# HEBoard_schematic_Ver3.net
KiCad netlist of a schematic drawn in Altium Designer
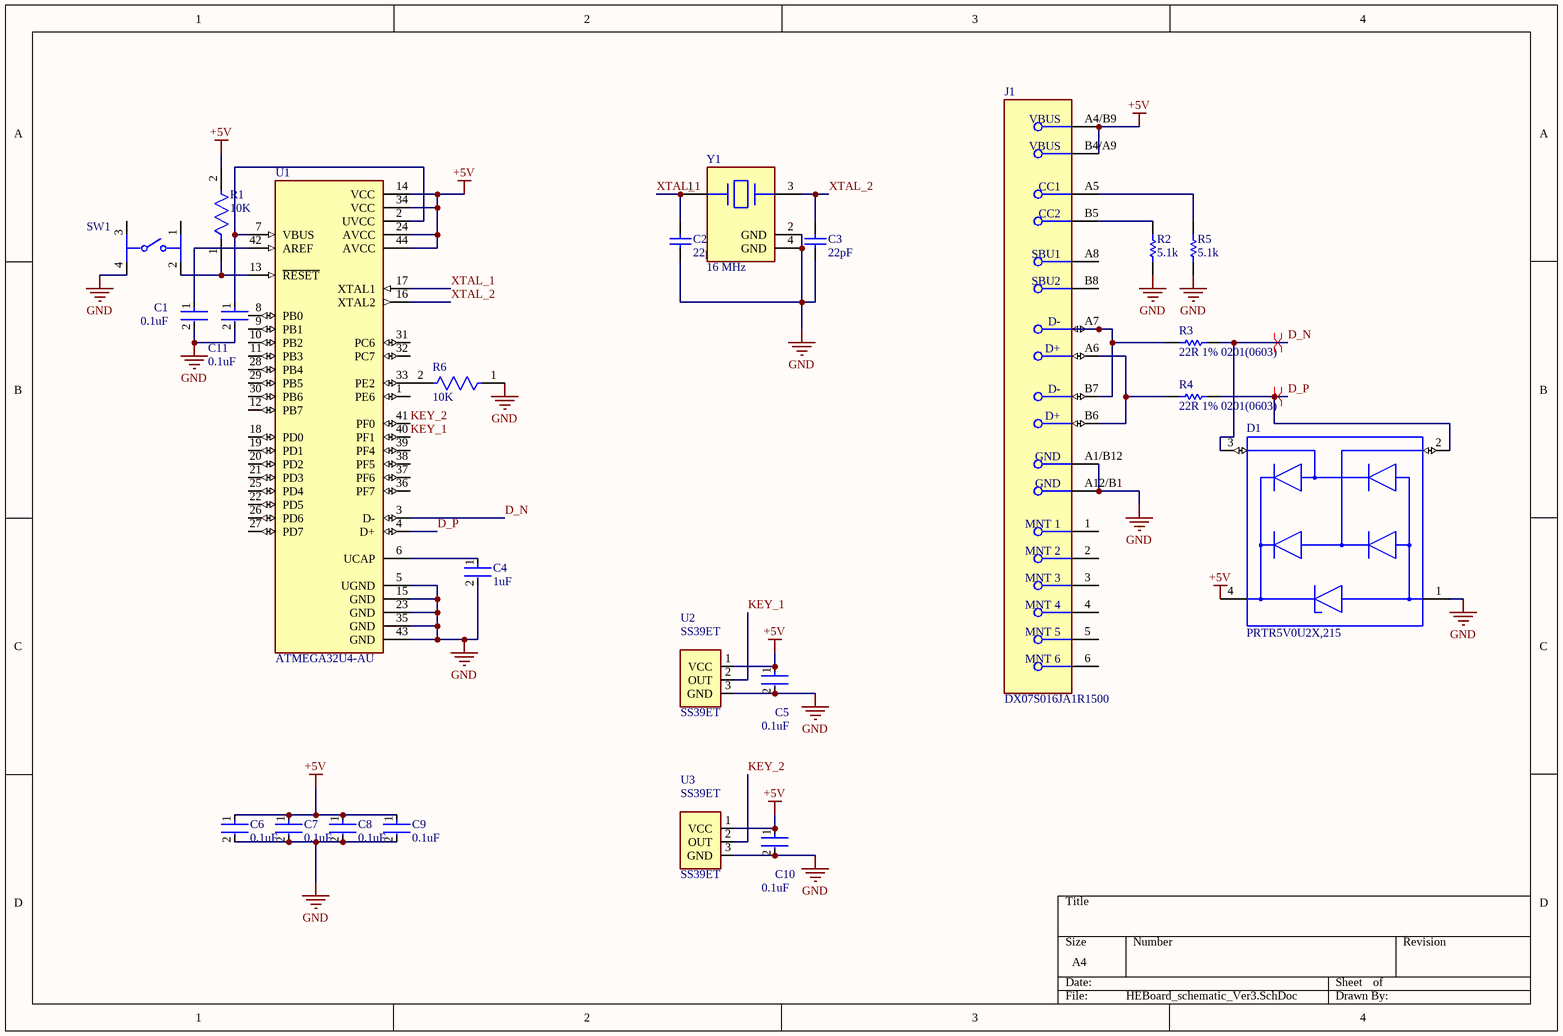
[diagram p0: HEBoard_schematic_Ver3.SchDoc]

(export (version "E")
  (design (tool "Eeschema 10.0.6"))
  (components
    (comp (ref "C1")
      (value "0.1uF")
      (footprint "FP-GRM033-0_03-IPC_C")
      (description "Chip Multilayer Ceramic Capacitors for General Purpose, 0201, 0.10uF, X5R, 15%, 10%, 10V")
      (fields (field (name "TOLERANCE") "10%") (field (name "VOLTAGE") "10V"))
      (libsource (lib "Altium Content Vault") (part "b4654b650e69147ec39a6b967a45e02"))
    )
    (comp (ref "C2")
      (value "22pF")
      (footprint "CAPC1006X50X20ML10T10")
      (fields
        (field (name "PART NUMBER") "0402ZK220GBSTR..")
        (field (name "MANUFACTURER") "AVX Interconnect / Elco")
      )
      (libsource (lib "Altium Content Vault") (part "CAP"))
    )
    (comp (ref "C3")
      (value "22pF")
      (footprint "CAPC1006X50X20ML10T10")
      (fields
        (field (name "PART NUMBER") "0402ZK220GBSTR..")
        (field (name "MANUFACTURER") "AVX Interconnect / Elco")
      )
      (libsource (lib "Altium Content Vault") (part "CAP"))
    )
    (comp (ref "C4")
      (value "1uF")
      (footprint "FP-GRM15-0_1-MFG")
      (description "CAP CER 1UF 10V X5R 0402")
      (fields
        (field (name "OCTOPART") "https://octopart.com/grm155r61a105ke15d-murata-197442")
        (field (name "MANUFACTURER PART NUMBER") "GRM155R61A105KE15D")
      )
      (libsource (lib "Altium Content Vault") (part "02cd4be3c70576c341d710602a673aa"))
    )
    (comp (ref "C5")
      (value "0.1uF")
      (footprint "FP-GRM033-0_03-IPC_C")
      (description "Chip Multilayer Ceramic Capacitors for General Purpose, 0201, 0.10uF, X5R, 15%, 10%, 10V")
      (fields (field (name "TOLERANCE") "10%") (field (name "VOLTAGE") "10V"))
      (libsource (lib "Altium Content Vault") (part "b4654b650e69147ec39a6b967a45e02"))
    )
    (comp (ref "C6")
      (value "0.1uF")
      (footprint "FP-CC0402-MFG")
      (description "CC0402 100 nF X7R 10.00% 10 V")
      (fields (field (name "MANUFACTURER") "YAGEO"))
      (libsource (lib "Altium Content Vault") (part "11868f565c42a9108669ba33697ecf6"))
    )
    (comp (ref "C7")
      (value "0.1uF")
      (footprint "FP-CC0402-MFG")
      (description "CC0402 100 nF X7R 10.00% 10 V")
      (fields (field (name "MANUFACTURER") "YAGEO"))
      (libsource (lib "Altium Content Vault") (part "11868f565c42a9108669ba33697ecf6"))
    )
    (comp (ref "C8")
      (value "0.1uF")
      (footprint "FP-CC0402-MFG")
      (description "CC0402 100 nF X7R 10.00% 10 V")
      (fields (field (name "MANUFACTURER") "YAGEO"))
      (libsource (lib "Altium Content Vault") (part "11868f565c42a9108669ba33697ecf6"))
    )
    (comp (ref "C9")
      (value "0.1uF")
      (footprint "FP-CC0402-MFG")
      (description "CC0402 100 nF X7R 10.00% 10 V")
      (fields (field (name "MANUFACTURER") "YAGEO"))
      (libsource (lib "Altium Content Vault") (part "11868f565c42a9108669ba33697ecf6"))
    )
    (comp (ref "C10")
      (value "0.1uF")
      (footprint "FP-GRM033-0_03-IPC_C")
      (description "Chip Multilayer Ceramic Capacitors for General Purpose, 0201, 0.10uF, X5R, 15%, 10%, 10V")
      (fields (field (name "TOLERANCE") "10%") (field (name "VOLTAGE") "10V"))
      (libsource (lib "Altium Content Vault") (part "b4654b650e69147ec39a6b967a45e02"))
    )
    (comp (ref "C11")
      (value "0.1uF")
      (footprint "FP-GRM033-0_03-IPC_C")
      (description "Chip Multilayer Ceramic Capacitors for General Purpose, 0201, 0.10uF, X5R, 15%, 10%, 10V")
      (fields (field (name "TOLERANCE") "10%") (field (name "VOLTAGE") "10V"))
      (libsource (lib "Altium Content Vault") (part "b4654b650e69147ec39a6b967a45e02"))
    )
    (comp (ref "D1")
      (value "PRTR5V0U2X,215")
      (footprint "FP-SOT143B-MFG")
      (description "TVS DIODE 5.5V SOT143B")
      (libsource (lib "Altium Content Vault") (part "31e4fa1655694efd507c8a671e666ef"))
    )
    (comp (ref "J1")
      (value "DX07S016JA1R1500")
      (footprint "FP-DX07S016JA1R1500-MFG")
      (description "CONN RCP USB2.0 TYP C 24P SMD RA")
      (libsource (lib "Altium Content Vault") (part "7f3e9989102a0f22bff9cb010881d34"))
    )
    (comp (ref "R1")
      (value "10K")
      (footprint "FP-CRGP0603-IPC_C")
      (description "CRGP 0603 10K 1%")
      (fields
        (field (name "OCTOPART") "https://octopart.com/crgp0603f10k-te+connectivity-91018721")
        (field (name "MANUFACTURER PART NUMBER") "CRGP0603F10K")
      )
      (libsource (lib "Altium Content Vault") (part "1029c3af85768c4190bb7ad29bc67b5"))
    )
    (comp (ref "R2")
      (value "5.1k")
      (footprint "RESC0603X26X15ML03T05")
      (fields (field (name "PART NUMBER") "ERJ1GNF5101C") (field (name "MANUFACTURER") "Panasonic"))
      (libsource (lib "Altium Content Vault") (part "RES"))
    )
    (comp (ref "R3")
      (value "22R 1% 0201(0603)")
      (footprint "RESC0201(0603)_M")
      (description "22R 0.05W 1% 0201 (0603 Metric)  SMD")
      (fields (field (name "POWER") "0.05 W") (field (name "TOLERANCE") "1 %"))
      (libsource (lib "Altium Content Vault") (part "RES"))
    )
    (comp (ref "R4")
      (value "22R 1% 0201(0603)")
      (footprint "RESC0201(0603)_M")
      (description "22R 0.05W 1% 0201 (0603 Metric)  SMD")
      (fields (field (name "POWER") "0.05 W") (field (name "TOLERANCE") "1 %"))
      (libsource (lib "Altium Content Vault") (part "RES"))
    )
    (comp (ref "R5")
      (value "5.1k")
      (footprint "RESC0603X26X15ML03T05")
      (fields (field (name "PART NUMBER") "ERJ1GNF5101C") (field (name "MANUFACTURER") "Panasonic"))
      (libsource (lib "Altium Content Vault") (part "RES"))
    )
    (comp (ref "R6")
      (value "10K")
      (footprint "FP-CRGP0603-IPC_C")
      (description "CRGP 0603 10K 1%")
      (fields
        (field (name "OCTOPART") "https://octopart.com/crgp0603f10k-te+connectivity-91018721")
        (field (name "MANUFACTURER PART NUMBER") "CRGP0603F10K")
      )
      (libsource (lib "Altium Content Vault") (part "1029c3af85768c4190bb7ad29bc67b5"))
    )
    (comp (ref "SW1")
      (value "~")
      (footprint "FP-PTS645SM43SMTR92LFS-MFG")
      (description "SWITCH TACTILE SPST-NO 0.05A 12V")
      (libsource (lib "Altium Content Vault") (part "1adf0dd01260c80cf25a44bfd6b99ba"))
    )
    (comp (ref "U1")
      (value "ATMEGA32U4-AU")
      (footprint "QFP80P1200X1200X120-44N")
      (description "AVR AVRÂ® ATmega Microcontroller IC 8-Bit 16MHz 32KB (16K x 16) FLASH 44-TQFP (10x10)")
      (fields (field (name "MF") "Microchip Technology"))
      (libsource (lib "Schlib1") (part "ATMEGA32U4-AU"))
    )
    (comp (ref "U2")
      (value "SS39ET")
      (footprint "CHRY-MX1A-11NW_V")
      (description "analog Hall Effect Sensor 1.5 mA 2.7 - 6.5 V dc ¦ Honeywell SS39ET")
      (fields (field (name "MF") "Honeywell Sensing and Productivity Solutions"))
      (libsource (lib "Schlib1") (part "SS39ET"))
    )
    (comp (ref "U3")
      (value "SS39ET")
      (footprint "CHRY-MX1A-11NW_V")
      (description "analog Hall Effect Sensor 1.5 mA 2.7 - 6.5 V dc ¦ Honeywell SS39ET")
      (fields (field (name "MF") "Honeywell Sensing and Productivity Solutions"))
      (libsource (lib "Schlib1") (part "SS39ET"))
    )
    (comp (ref "Y1")
      (value "16 MHz")
      (footprint "FP-ABM8G-MFG")
      (description "Crystal 16MHz ±30ppm (Tol) ±30ppm (Stability) 10pF FUND 80Ω 4-Pin SMD T/R")
      (libsource (lib "Altium Content Vault") (part "48e526d86b7f2615d98721063c72f49"))
    )
  )
  (nets
    (net (code "1") (name "+5V") (class "Default")
      (node (ref "C10") (pin "1") (pinfunction "1_1") (pintype "passive"))
      (node (ref "C5") (pin "1") (pinfunction "1_1") (pintype "passive"))
      (node (ref "C6") (pin "1") (pinfunction "1_1") (pintype "passive"))
      (node (ref "C7") (pin "1") (pinfunction "1_1") (pintype "passive"))
      (node (ref "C8") (pin "1") (pinfunction "1_1") (pintype "passive"))
      (node (ref "C9") (pin "1") (pinfunction "1_1") (pintype "passive"))
      (node (ref "D1") (pin "4") (pinfunction "VCC_4") (pintype "power_in"))
      (node (ref "J1") (pin "A4/B9") (pinfunction "VBUS_A4/B9") (pintype "power_in"))
      (node (ref "J1") (pin "B4/A9") (pinfunction "VBUS_B4/A9") (pintype "power_in"))
      (node (ref "R1") (pin "2") (pinfunction "2_2") (pintype "passive"))
      (node (ref "U1") (pin "14") (pinfunction "VCC_14") (pintype "power_in"))
      (node (ref "U1") (pin "24") (pinfunction "AVCC_24") (pintype "power_in"))
      (node (ref "U1") (pin "34") (pinfunction "VCC_34") (pintype "power_in"))
      (node (ref "U1") (pin "44") (pinfunction "AVCC_44") (pintype "power_in"))
      (node (ref "U2") (pin "1") (pinfunction "VCC_1") (pintype "passive"))
      (node (ref "U3") (pin "1") (pinfunction "VCC_1") (pintype "passive"))
    )
    (net (code "2") (name "/D_N") (class "Default")
      (node (ref "D1") (pin "3") (pinfunction "I/O_2_3") (pintype "bidirectional"))
      (node (ref "R3") (pin "2") (pinfunction "2_2") (pintype "passive"))
      (node (ref "U1") (pin "3") (pinfunction "D-_3") (pintype "bidirectional"))
    )
    (net (code "3") (name "/D_P") (class "Default")
      (node (ref "D1") (pin "2") (pinfunction "I/O_1_2") (pintype "bidirectional"))
      (node (ref "R4") (pin "2") (pinfunction "2_2") (pintype "passive"))
      (node (ref "U1") (pin "4") (pinfunction "D+_4") (pintype "bidirectional"))
    )
    (net (code "4") (name "/KEY_1") (class "Default")
      (node (ref "U1") (pin "40") (pinfunction "PF1_40") (pintype "bidirectional"))
      (node (ref "U2") (pin "2") (pinfunction "OUT_2") (pintype "passive"))
    )
    (net (code "5") (name "/KEY_2") (class "Default")
      (node (ref "U1") (pin "41") (pinfunction "PF0_41") (pintype "bidirectional"))
      (node (ref "U3") (pin "2") (pinfunction "OUT_2") (pintype "passive"))
    )
    (net (code "6") (name "/XTAL_1") (class "Default")
      (node (ref "C2") (pin "2") (pinfunction "2_2") (pintype "passive"))
      (node (ref "U1") (pin "17") (pinfunction "XTAL1_17") (pintype "input"))
      (node (ref "Y1") (pin "1") (pinfunction "1_1") (pintype "passive"))
    )
    (net (code "7") (name "/XTAL_2") (class "Default")
      (node (ref "C3") (pin "2") (pinfunction "2_2") (pintype "passive"))
      (node (ref "U1") (pin "16") (pinfunction "XTAL2_16") (pintype "output"))
      (node (ref "Y1") (pin "3") (pinfunction "3_3") (pintype "passive"))
    )
    (net (code "8") (name "GND") (class "Default")
      (node (ref "C1") (pin "2") (pinfunction "2_2") (pintype "passive"))
      (node (ref "C10") (pin "2") (pinfunction "2_2") (pintype "passive"))
      (node (ref "C11") (pin "2") (pinfunction "2_2") (pintype "passive"))
      (node (ref "C2") (pin "1") (pinfunction "1_1") (pintype "passive"))
      (node (ref "C3") (pin "1") (pinfunction "1_1") (pintype "passive"))
      (node (ref "C4") (pin "2") (pinfunction "2_2") (pintype "passive"))
      (node (ref "C5") (pin "2") (pinfunction "2_2") (pintype "passive"))
      (node (ref "C6") (pin "2") (pinfunction "2_2") (pintype "passive"))
      (node (ref "C7") (pin "2") (pinfunction "2_2") (pintype "passive"))
      (node (ref "C8") (pin "2") (pinfunction "2_2") (pintype "passive"))
      (node (ref "C9") (pin "2") (pinfunction "2_2") (pintype "passive"))
      (node (ref "D1") (pin "1") (pinfunction "GND_1") (pintype "power_in"))
      (node (ref "J1") (pin "A1/B12") (pinfunction "GND_A1/B12") (pintype "power_in"))
      (node (ref "J1") (pin "A12/B1") (pinfunction "GND_A12/B1") (pintype "power_in"))
      (node (ref "R2") (pin "1") (pinfunction "1_1") (pintype "passive"))
      (node (ref "R5") (pin "1") (pinfunction "1_1") (pintype "passive"))
      (node (ref "R6") (pin "1") (pinfunction "1_1") (pintype "passive"))
      (node (ref "SW1") (pin "4") (pinfunction "4_4") (pintype "passive"))
      (node (ref "U1") (pin "15") (pinfunction "GND_15") (pintype "power_in"))
      (node (ref "U1") (pin "23") (pinfunction "GND_23") (pintype "power_in"))
      (node (ref "U1") (pin "35") (pinfunction "GND_35") (pintype "power_in"))
      (node (ref "U1") (pin "43") (pinfunction "GND_43") (pintype "power_in"))
      (node (ref "U1") (pin "5") (pinfunction "UGND_5") (pintype "power_in"))
      (node (ref "U2") (pin "3") (pinfunction "GND_3") (pintype "passive"))
      (node (ref "U3") (pin "3") (pinfunction "GND_3") (pintype "passive"))
      (node (ref "Y1") (pin "2") (pinfunction "GND_2") (pintype "power_in"))
      (node (ref "Y1") (pin "4") (pinfunction "GND_4") (pintype "power_in"))
    )
    (net (code "9") (name "Net-(J1-CC1)") (class "Default")
      (node (ref "J1") (pin "A5") (pinfunction "CC1_A5") (pintype "passive"))
      (node (ref "R5") (pin "2") (pinfunction "2_2") (pintype "passive"))
    )
    (net (code "10") (name "Net-(J1-CC2)") (class "Default")
      (node (ref "J1") (pin "B5") (pinfunction "CC2_B5") (pintype "passive"))
      (node (ref "R2") (pin "2") (pinfunction "2_2") (pintype "passive"))
    )
    (net (code "11") (name "Net-(J1-D+-PadA6)") (class "Default")
      (node (ref "J1") (pin "A6") (pinfunction "D+_A6") (pintype "bidirectional"))
      (node (ref "J1") (pin "B6") (pinfunction "D+_B6") (pintype "bidirectional"))
      (node (ref "R4") (pin "1") (pinfunction "1_1") (pintype "passive"))
    )
    (net (code "12") (name "Net-(J1-D--PadA7)") (class "Default")
      (node (ref "J1") (pin "A7") (pinfunction "D-_A7") (pintype "bidirectional"))
      (node (ref "J1") (pin "B7") (pinfunction "D-_B7") (pintype "bidirectional"))
      (node (ref "R3") (pin "1") (pinfunction "1_1") (pintype "passive"))
    )
    (net (code "13") (name "Net-(U1-AREF)") (class "Default")
      (node (ref "C1") (pin "1") (pinfunction "1_1") (pintype "passive"))
      (node (ref "U1") (pin "42") (pinfunction "AREF_42") (pintype "input"))
    )
    (net (code "14") (name "Net-(U1-PE2)") (class "Default")
      (node (ref "R6") (pin "2") (pinfunction "2_2") (pintype "passive"))
      (node (ref "U1") (pin "33") (pinfunction "PE2_33") (pintype "bidirectional"))
    )
    (net (code "15") (name "Net-(U1-UCAP)") (class "Default")
      (node (ref "C4") (pin "1") (pinfunction "1_1") (pintype "passive"))
      (node (ref "U1") (pin "6") (pinfunction "UCAP_6") (pintype "passive"))
    )
    (net (code "16") (name "Net-(U1-UVCC)") (class "Default")
      (node (ref "C11") (pin "1") (pinfunction "1_1") (pintype "passive"))
      (node (ref "U1") (pin "2") (pinfunction "UVCC_2") (pintype "power_in"))
      (node (ref "U1") (pin "7") (pinfunction "VBUS_7") (pintype "input"))
    )
    (net (code "17") (name "Net-(U1-~{RESET})") (class "Default")
      (node (ref "R1") (pin "1") (pinfunction "1_1") (pintype "passive"))
      (node (ref "SW1") (pin "2") (pinfunction "2_2") (pintype "passive"))
      (node (ref "U1") (pin "13") (pinfunction "~{RESET}_13") (pintype "input"))
    )
    (net (code "18") (name "unconnected-(J1-MNT_1-Pad1)") (class "Default")
      (node (ref "J1") (pin "1") (pinfunction "MNT_1_1") (pintype "passive"))
    )
    (net (code "19") (name "unconnected-(J1-MNT_2-Pad2)") (class "Default")
      (node (ref "J1") (pin "2") (pinfunction "MNT_2_2") (pintype "passive"))
    )
    (net (code "20") (name "unconnected-(J1-MNT_3-Pad3)") (class "Default")
      (node (ref "J1") (pin "3") (pinfunction "MNT_3_3") (pintype "passive"))
    )
    (net (code "21") (name "unconnected-(J1-MNT_4-Pad4)") (class "Default")
      (node (ref "J1") (pin "4") (pinfunction "MNT_4_4") (pintype "passive"))
    )
    (net (code "22") (name "unconnected-(J1-MNT_5-Pad5)") (class "Default")
      (node (ref "J1") (pin "5") (pinfunction "MNT_5_5") (pintype "passive"))
    )
    (net (code "23") (name "unconnected-(J1-MNT_6-Pad6)") (class "Default")
      (node (ref "J1") (pin "6") (pinfunction "MNT_6_6") (pintype "passive"))
    )
    (net (code "24") (name "unconnected-(J1-SBU1-PadA8)") (class "Default")
      (node (ref "J1") (pin "A8") (pinfunction "SBU1_A8") (pintype "passive"))
    )
    (net (code "25") (name "unconnected-(J1-SBU2-PadB8)") (class "Default")
      (node (ref "J1") (pin "B8") (pinfunction "SBU2_B8") (pintype "passive"))
    )
    (net (code "26") (name "unconnected-(SW1-Pad1)") (class "Default")
      (node (ref "SW1") (pin "1") (pinfunction "1_1") (pintype "passive"))
    )
    (net (code "27") (name "unconnected-(SW1-Pad3)") (class "Default")
      (node (ref "SW1") (pin "3") (pinfunction "3_3") (pintype "passive"))
    )
    (net (code "28") (name "unconnected-(U1-PB0-Pad8)") (class "Default")
      (node (ref "U1") (pin "8") (pinfunction "PB0_8") (pintype "bidirectional"))
    )
    (net (code "29") (name "unconnected-(U1-PB1-Pad9)") (class "Default")
      (node (ref "U1") (pin "9") (pinfunction "PB1_9") (pintype "bidirectional"))
    )
    (net (code "30") (name "unconnected-(U1-PB2-Pad10)") (class "Default")
      (node (ref "U1") (pin "10") (pinfunction "PB2_10") (pintype "bidirectional"))
    )
    (net (code "31") (name "unconnected-(U1-PB3-Pad11)") (class "Default")
      (node (ref "U1") (pin "11") (pinfunction "PB3_11") (pintype "bidirectional"))
    )
    (net (code "32") (name "unconnected-(U1-PB4-Pad28)") (class "Default")
      (node (ref "U1") (pin "28") (pinfunction "PB4_28") (pintype "bidirectional"))
    )
    (net (code "33") (name "unconnected-(U1-PB5-Pad29)") (class "Default")
      (node (ref "U1") (pin "29") (pinfunction "PB5_29") (pintype "bidirectional"))
    )
    (net (code "34") (name "unconnected-(U1-PB6-Pad30)") (class "Default")
      (node (ref "U1") (pin "30") (pinfunction "PB6_30") (pintype "bidirectional"))
    )
    (net (code "35") (name "unconnected-(U1-PB7-Pad12)") (class "Default")
      (node (ref "U1") (pin "12") (pinfunction "PB7_12") (pintype "bidirectional"))
    )
    (net (code "36") (name "unconnected-(U1-PC6-Pad31)") (class "Default")
      (node (ref "U1") (pin "31") (pinfunction "PC6_31") (pintype "bidirectional"))
    )
    (net (code "37") (name "unconnected-(U1-PC7-Pad32)") (class "Default")
      (node (ref "U1") (pin "32") (pinfunction "PC7_32") (pintype "bidirectional"))
    )
    (net (code "38") (name "unconnected-(U1-PD0-Pad18)") (class "Default")
      (node (ref "U1") (pin "18") (pinfunction "PD0_18") (pintype "bidirectional"))
    )
    (net (code "39") (name "unconnected-(U1-PD1-Pad19)") (class "Default")
      (node (ref "U1") (pin "19") (pinfunction "PD1_19") (pintype "bidirectional"))
    )
    (net (code "40") (name "unconnected-(U1-PD2-Pad20)") (class "Default")
      (node (ref "U1") (pin "20") (pinfunction "PD2_20") (pintype "bidirectional"))
    )
    (net (code "41") (name "unconnected-(U1-PD3-Pad21)") (class "Default")
      (node (ref "U1") (pin "21") (pinfunction "PD3_21") (pintype "bidirectional"))
    )
    (net (code "42") (name "unconnected-(U1-PD4-Pad25)") (class "Default")
      (node (ref "U1") (pin "25") (pinfunction "PD4_25") (pintype "bidirectional"))
    )
    (net (code "43") (name "unconnected-(U1-PD5-Pad22)") (class "Default")
      (node (ref "U1") (pin "22") (pinfunction "PD5_22") (pintype "bidirectional"))
    )
    (net (code "44") (name "unconnected-(U1-PD6-Pad26)") (class "Default")
      (node (ref "U1") (pin "26") (pinfunction "PD6_26") (pintype "bidirectional"))
    )
    (net (code "45") (name "unconnected-(U1-PD7-Pad27)") (class "Default")
      (node (ref "U1") (pin "27") (pinfunction "PD7_27") (pintype "bidirectional"))
    )
    (net (code "46") (name "unconnected-(U1-PE6-Pad1)") (class "Default")
      (node (ref "U1") (pin "1") (pinfunction "PE6_1") (pintype "bidirectional"))
    )
    (net (code "47") (name "unconnected-(U1-PF4-Pad39)") (class "Default")
      (node (ref "U1") (pin "39") (pinfunction "PF4_39") (pintype "bidirectional"))
    )
    (net (code "48") (name "unconnected-(U1-PF5-Pad38)") (class "Default")
      (node (ref "U1") (pin "38") (pinfunction "PF5_38") (pintype "bidirectional"))
    )
    (net (code "49") (name "unconnected-(U1-PF6-Pad37)") (class "Default")
      (node (ref "U1") (pin "37") (pinfunction "PF6_37") (pintype "bidirectional"))
    )
    (net (code "50") (name "unconnected-(U1-PF7-Pad36)") (class "Default")
      (node (ref "U1") (pin "36") (pinfunction "PF7_36") (pintype "bidirectional"))
    )
  )
)
